# ir.net
KiCad netlist of a schematic drawn in EAGLE
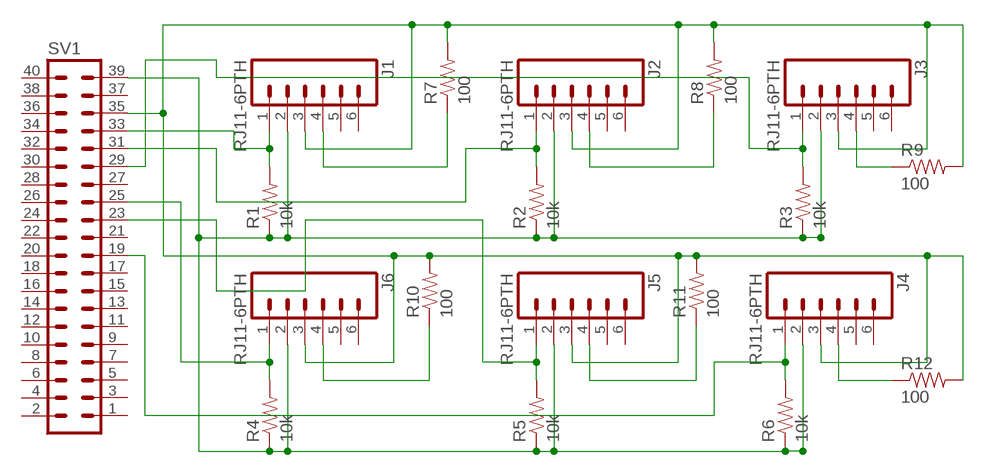
[diagram p0: schematic, sheet 1]

(export (version "E")
  (design (tool "Eeschema 10.0.6"))
  (components
    (comp (ref "J1")
      (value "RJ11-6PTH")
      (footprint "eagle-import:RJ11-6")
      (libsource (lib "eagle-import") (part "RJ11-6PTH"))
    )
    (comp (ref "J2")
      (value "RJ11-6PTH")
      (footprint "eagle-import:RJ11-6")
      (libsource (lib "eagle-import") (part "RJ11-6PTH"))
    )
    (comp (ref "J3")
      (value "RJ11-6PTH")
      (footprint "eagle-import:RJ11-6")
      (libsource (lib "eagle-import") (part "RJ11-6PTH"))
    )
    (comp (ref "J4")
      (value "RJ11-6PTH")
      (footprint "eagle-import:RJ11-6")
      (libsource (lib "eagle-import") (part "RJ11-6PTH"))
    )
    (comp (ref "J5")
      (value "RJ11-6PTH")
      (footprint "eagle-import:RJ11-6")
      (libsource (lib "eagle-import") (part "RJ11-6PTH"))
    )
    (comp (ref "J6")
      (value "RJ11-6PTH")
      (footprint "eagle-import:RJ11-6")
      (libsource (lib "eagle-import") (part "RJ11-6PTH"))
    )
    (comp (ref "R1")
      (value "10k")
      (footprint "eagle-import:AXIAL-0.3")
      (libsource (lib "eagle-import") (part "10KOHM-1/4W-1%(PTH)HORIZ"))
    )
    (comp (ref "R2")
      (value "10k")
      (footprint "eagle-import:AXIAL-0.3")
      (libsource (lib "eagle-import") (part "10KOHM-1/4W-1%(PTH)HORIZ"))
    )
    (comp (ref "R3")
      (value "10k")
      (footprint "eagle-import:AXIAL-0.3")
      (libsource (lib "eagle-import") (part "10KOHM-1/4W-1%(PTH)HORIZ"))
    )
    (comp (ref "R4")
      (value "10k")
      (footprint "eagle-import:AXIAL-0.3")
      (libsource (lib "eagle-import") (part "10KOHM-1/4W-1%(PTH)HORIZ"))
    )
    (comp (ref "R5")
      (value "10k")
      (footprint "eagle-import:AXIAL-0.3")
      (libsource (lib "eagle-import") (part "10KOHM-1/4W-1%(PTH)HORIZ"))
    )
    (comp (ref "R6")
      (value "10k")
      (footprint "eagle-import:AXIAL-0.3")
      (libsource (lib "eagle-import") (part "10KOHM-1/4W-1%(PTH)HORIZ"))
    )
    (comp (ref "R7")
      (value "100")
      (footprint "eagle-import:AXIAL-0.3")
      (libsource (lib "eagle-import") (part "100OHM1/4W5%(PTH)"))
    )
    (comp (ref "R8")
      (value "100")
      (footprint "eagle-import:AXIAL-0.3")
      (libsource (lib "eagle-import") (part "100OHM1/4W5%(PTH)"))
    )
    (comp (ref "R9")
      (value "100")
      (footprint "eagle-import:AXIAL-0.3")
      (libsource (lib "eagle-import") (part "100OHM1/4W5%(PTH)"))
    )
    (comp (ref "R10")
      (value "100")
      (footprint "eagle-import:AXIAL-0.3")
      (libsource (lib "eagle-import") (part "100OHM1/4W5%(PTH)"))
    )
    (comp (ref "R11")
      (value "100")
      (footprint "eagle-import:AXIAL-0.3")
      (libsource (lib "eagle-import") (part "100OHM1/4W5%(PTH)"))
    )
    (comp (ref "R12")
      (value "100")
      (footprint "eagle-import:AXIAL-0.3")
      (libsource (lib "eagle-import") (part "100OHM1/4W5%(PTH)"))
    )
    (comp (ref "SV1")
      (value "MA20-2")
      (footprint "eagle-import:MA20-2")
      (libsource (lib "eagle-import") (part "MA20-2"))
    )
  )
  (nets
    (net (code "1") (name "Net-(R1-1)") (class "Default")
      (node (ref "J1") (pin "2") (pinfunction "2_2") (pintype "passive"))
      (node (ref "J2") (pin "2") (pinfunction "2_2") (pintype "passive"))
      (node (ref "J3") (pin "2") (pinfunction "2_2") (pintype "passive"))
      (node (ref "J4") (pin "2") (pinfunction "2_2") (pintype "passive"))
      (node (ref "J5") (pin "2") (pinfunction "2_2") (pintype "passive"))
      (node (ref "J6") (pin "2") (pinfunction "2_2") (pintype "passive"))
      (node (ref "R1") (pin "P$1") (pinfunction "1_P$1") (pintype "passive"))
      (node (ref "R2") (pin "P$1") (pinfunction "1_P$1") (pintype "passive"))
      (node (ref "R3") (pin "P$1") (pinfunction "1_P$1") (pintype "passive"))
      (node (ref "R4") (pin "P$1") (pinfunction "1_P$1") (pintype "passive"))
      (node (ref "R5") (pin "P$1") (pinfunction "1_P$1") (pintype "passive"))
      (node (ref "R6") (pin "P$1") (pinfunction "1_P$1") (pintype "passive"))
      (node (ref "SV1") (pin "39") (pinfunction "39_39") (pintype "passive"))
    )
    (net (code "2") (name "Net-(R1-2)") (class "Default")
      (node (ref "J1") (pin "1") (pinfunction "1_1") (pintype "passive"))
      (node (ref "R1") (pin "P$2") (pinfunction "2_P$2") (pintype "passive"))
      (node (ref "SV1") (pin "33") (pinfunction "33_33") (pintype "passive"))
    )
    (net (code "3") (name "Net-(R2-2)") (class "Default")
      (node (ref "J2") (pin "1") (pinfunction "1_1") (pintype "passive"))
      (node (ref "R2") (pin "P$2") (pinfunction "2_P$2") (pintype "passive"))
      (node (ref "SV1") (pin "31") (pinfunction "31_31") (pintype "passive"))
    )
    (net (code "4") (name "Net-(R3-2)") (class "Default")
      (node (ref "J3") (pin "1") (pinfunction "1_1") (pintype "passive"))
      (node (ref "R3") (pin "P$2") (pinfunction "2_P$2") (pintype "passive"))
      (node (ref "SV1") (pin "29") (pinfunction "29_29") (pintype "passive"))
    )
    (net (code "5") (name "Net-(R4-2)") (class "Default")
      (node (ref "J6") (pin "1") (pinfunction "1_1") (pintype "passive"))
      (node (ref "R4") (pin "P$2") (pinfunction "2_P$2") (pintype "passive"))
      (node (ref "SV1") (pin "25") (pinfunction "25_25") (pintype "passive"))
    )
    (net (code "6") (name "Net-(R5-2)") (class "Default")
      (node (ref "J5") (pin "1") (pinfunction "1_1") (pintype "passive"))
      (node (ref "R5") (pin "P$2") (pinfunction "2_P$2") (pintype "passive"))
      (node (ref "SV1") (pin "23") (pinfunction "23_23") (pintype "passive"))
    )
    (net (code "7") (name "Net-(R6-2)") (class "Default")
      (node (ref "J4") (pin "1") (pinfunction "1_1") (pintype "passive"))
      (node (ref "R6") (pin "P$2") (pinfunction "2_P$2") (pintype "passive"))
      (node (ref "SV1") (pin "19") (pinfunction "19_19") (pintype "passive"))
    )
    (net (code "8") (name "Net-(R7-1)") (class "Default")
      (node (ref "J1") (pin "4") (pinfunction "4_4") (pintype "passive"))
      (node (ref "R7") (pin "P$1") (pinfunction "1_P$1") (pintype "passive"))
    )
    (net (code "9") (name "Net-(R8-1)") (class "Default")
      (node (ref "J2") (pin "4") (pinfunction "4_4") (pintype "passive"))
      (node (ref "R8") (pin "P$1") (pinfunction "1_P$1") (pintype "passive"))
    )
    (net (code "10") (name "Net-(R9-1)") (class "Default")
      (node (ref "J3") (pin "4") (pinfunction "4_4") (pintype "passive"))
      (node (ref "R9") (pin "P$1") (pinfunction "1_P$1") (pintype "passive"))
    )
    (net (code "11") (name "Net-(R10-1)") (class "Default")
      (node (ref "J6") (pin "4") (pinfunction "4_4") (pintype "passive"))
      (node (ref "R10") (pin "P$1") (pinfunction "1_P$1") (pintype "passive"))
    )
    (net (code "12") (name "Net-(R10-2)") (class "Default")
      (node (ref "J1") (pin "3") (pinfunction "3_3") (pintype "passive"))
      (node (ref "J2") (pin "3") (pinfunction "3_3") (pintype "passive"))
      (node (ref "J3") (pin "3") (pinfunction "3_3") (pintype "passive"))
      (node (ref "J4") (pin "3") (pinfunction "3_3") (pintype "passive"))
      (node (ref "J5") (pin "3") (pinfunction "3_3") (pintype "passive"))
      (node (ref "J6") (pin "3") (pinfunction "3_3") (pintype "passive"))
      (node (ref "R10") (pin "P$2") (pinfunction "2_P$2") (pintype "passive"))
      (node (ref "R11") (pin "P$2") (pinfunction "2_P$2") (pintype "passive"))
      (node (ref "R12") (pin "P$2") (pinfunction "2_P$2") (pintype "passive"))
      (node (ref "R7") (pin "P$2") (pinfunction "2_P$2") (pintype "passive"))
      (node (ref "R8") (pin "P$2") (pinfunction "2_P$2") (pintype "passive"))
      (node (ref "R9") (pin "P$2") (pinfunction "2_P$2") (pintype "passive"))
      (node (ref "SV1") (pin "35") (pinfunction "35_35") (pintype "passive"))
    )
    (net (code "13") (name "Net-(R11-1)") (class "Default")
      (node (ref "J5") (pin "4") (pinfunction "4_4") (pintype "passive"))
      (node (ref "R11") (pin "P$1") (pinfunction "1_P$1") (pintype "passive"))
    )
    (net (code "14") (name "Net-(R12-1)") (class "Default")
      (node (ref "J4") (pin "4") (pinfunction "4_4") (pintype "passive"))
      (node (ref "R12") (pin "P$1") (pinfunction "1_P$1") (pintype "passive"))
    )
    (net (code "15") (name "unconnected-(J1-Pad5)") (class "Default")
      (node (ref "J1") (pin "5") (pinfunction "5_5") (pintype "passive"))
    )
    (net (code "16") (name "unconnected-(J1-Pad6)") (class "Default")
      (node (ref "J1") (pin "6") (pinfunction "6_6") (pintype "passive"))
    )
    (net (code "17") (name "unconnected-(J2-Pad5)") (class "Default")
      (node (ref "J2") (pin "5") (pinfunction "5_5") (pintype "passive"))
    )
    (net (code "18") (name "unconnected-(J2-Pad6)") (class "Default")
      (node (ref "J2") (pin "6") (pinfunction "6_6") (pintype "passive"))
    )
    (net (code "19") (name "unconnected-(J3-Pad5)") (class "Default")
      (node (ref "J3") (pin "5") (pinfunction "5_5") (pintype "passive"))
    )
    (net (code "20") (name "unconnected-(J3-Pad6)") (class "Default")
      (node (ref "J3") (pin "6") (pinfunction "6_6") (pintype "passive"))
    )
    (net (code "21") (name "unconnected-(J4-Pad5)") (class "Default")
      (node (ref "J4") (pin "5") (pinfunction "5_5") (pintype "passive"))
    )
    (net (code "22") (name "unconnected-(J4-Pad6)") (class "Default")
      (node (ref "J4") (pin "6") (pinfunction "6_6") (pintype "passive"))
    )
    (net (code "23") (name "unconnected-(J5-Pad5)") (class "Default")
      (node (ref "J5") (pin "5") (pinfunction "5_5") (pintype "passive"))
    )
    (net (code "24") (name "unconnected-(J5-Pad6)") (class "Default")
      (node (ref "J5") (pin "6") (pinfunction "6_6") (pintype "passive"))
    )
    (net (code "25") (name "unconnected-(J6-Pad5)") (class "Default")
      (node (ref "J6") (pin "5") (pinfunction "5_5") (pintype "passive"))
    )
    (net (code "26") (name "unconnected-(J6-Pad6)") (class "Default")
      (node (ref "J6") (pin "6") (pinfunction "6_6") (pintype "passive"))
    )
    (net (code "27") (name "unconnected-(SV1-Pad1)") (class "Default")
      (node (ref "SV1") (pin "1") (pinfunction "1_1") (pintype "passive"))
    )
    (net (code "28") (name "unconnected-(SV1-Pad2)") (class "Default")
      (node (ref "SV1") (pin "2") (pinfunction "2_2") (pintype "passive"))
    )
    (net (code "29") (name "unconnected-(SV1-Pad3)") (class "Default")
      (node (ref "SV1") (pin "3") (pinfunction "3_3") (pintype "passive"))
    )
    (net (code "30") (name "unconnected-(SV1-Pad4)") (class "Default")
      (node (ref "SV1") (pin "4") (pinfunction "4_4") (pintype "passive"))
    )
    (net (code "31") (name "unconnected-(SV1-Pad5)") (class "Default")
      (node (ref "SV1") (pin "5") (pinfunction "5_5") (pintype "passive"))
    )
    (net (code "32") (name "unconnected-(SV1-Pad6)") (class "Default")
      (node (ref "SV1") (pin "6") (pinfunction "6_6") (pintype "passive"))
    )
    (net (code "33") (name "unconnected-(SV1-Pad7)") (class "Default")
      (node (ref "SV1") (pin "7") (pinfunction "7_7") (pintype "passive"))
    )
    (net (code "34") (name "unconnected-(SV1-Pad8)") (class "Default")
      (node (ref "SV1") (pin "8") (pinfunction "8_8") (pintype "passive"))
    )
    (net (code "35") (name "unconnected-(SV1-Pad9)") (class "Default")
      (node (ref "SV1") (pin "9") (pinfunction "9_9") (pintype "passive"))
    )
    (net (code "36") (name "unconnected-(SV1-Pad10)") (class "Default")
      (node (ref "SV1") (pin "10") (pinfunction "10_10") (pintype "passive"))
    )
    (net (code "37") (name "unconnected-(SV1-Pad11)") (class "Default")
      (node (ref "SV1") (pin "11") (pinfunction "11_11") (pintype "passive"))
    )
    (net (code "38") (name "unconnected-(SV1-Pad12)") (class "Default")
      (node (ref "SV1") (pin "12") (pinfunction "12_12") (pintype "passive"))
    )
    (net (code "39") (name "unconnected-(SV1-Pad13)") (class "Default")
      (node (ref "SV1") (pin "13") (pinfunction "13_13") (pintype "passive"))
    )
    (net (code "40") (name "unconnected-(SV1-Pad14)") (class "Default")
      (node (ref "SV1") (pin "14") (pinfunction "14_14") (pintype "passive"))
    )
    (net (code "41") (name "unconnected-(SV1-Pad15)") (class "Default")
      (node (ref "SV1") (pin "15") (pinfunction "15_15") (pintype "passive"))
    )
    (net (code "42") (name "unconnected-(SV1-Pad16)") (class "Default")
      (node (ref "SV1") (pin "16") (pinfunction "16_16") (pintype "passive"))
    )
    (net (code "43") (name "unconnected-(SV1-Pad17)") (class "Default")
      (node (ref "SV1") (pin "17") (pinfunction "17_17") (pintype "passive"))
    )
    (net (code "44") (name "unconnected-(SV1-Pad18)") (class "Default")
      (node (ref "SV1") (pin "18") (pinfunction "18_18") (pintype "passive"))
    )
    (net (code "45") (name "unconnected-(SV1-Pad20)") (class "Default")
      (node (ref "SV1") (pin "20") (pinfunction "20_20") (pintype "passive"))
    )
    (net (code "46") (name "unconnected-(SV1-Pad21)") (class "Default")
      (node (ref "SV1") (pin "21") (pinfunction "21_21") (pintype "passive"))
    )
    (net (code "47") (name "unconnected-(SV1-Pad22)") (class "Default")
      (node (ref "SV1") (pin "22") (pinfunction "22_22") (pintype "passive"))
    )
    (net (code "48") (name "unconnected-(SV1-Pad24)") (class "Default")
      (node (ref "SV1") (pin "24") (pinfunction "24_24") (pintype "passive"))
    )
    (net (code "49") (name "unconnected-(SV1-Pad26)") (class "Default")
      (node (ref "SV1") (pin "26") (pinfunction "26_26") (pintype "passive"))
    )
    (net (code "50") (name "unconnected-(SV1-Pad27)") (class "Default")
      (node (ref "SV1") (pin "27") (pinfunction "27_27") (pintype "passive"))
    )
    (net (code "51") (name "unconnected-(SV1-Pad28)") (class "Default")
      (node (ref "SV1") (pin "28") (pinfunction "28_28") (pintype "passive"))
    )
    (net (code "52") (name "unconnected-(SV1-Pad30)") (class "Default")
      (node (ref "SV1") (pin "30") (pinfunction "30_30") (pintype "passive"))
    )
    (net (code "53") (name "unconnected-(SV1-Pad32)") (class "Default")
      (node (ref "SV1") (pin "32") (pinfunction "32_32") (pintype "passive"))
    )
    (net (code "54") (name "unconnected-(SV1-Pad34)") (class "Default")
      (node (ref "SV1") (pin "34") (pinfunction "34_34") (pintype "passive"))
    )
    (net (code "55") (name "unconnected-(SV1-Pad36)") (class "Default")
      (node (ref "SV1") (pin "36") (pinfunction "36_36") (pintype "passive"))
    )
    (net (code "56") (name "unconnected-(SV1-Pad37)") (class "Default")
      (node (ref "SV1") (pin "37") (pinfunction "37_37") (pintype "passive"))
    )
    (net (code "57") (name "unconnected-(SV1-Pad38)") (class "Default")
      (node (ref "SV1") (pin "38") (pinfunction "38_38") (pintype "passive"))
    )
    (net (code "58") (name "unconnected-(SV1-Pad40)") (class "Default")
      (node (ref "SV1") (pin "40") (pinfunction "40_40") (pintype "passive"))
    )
  )
)
